# PS.net
KiCad netlist of a schematic drawn in Altium Designer
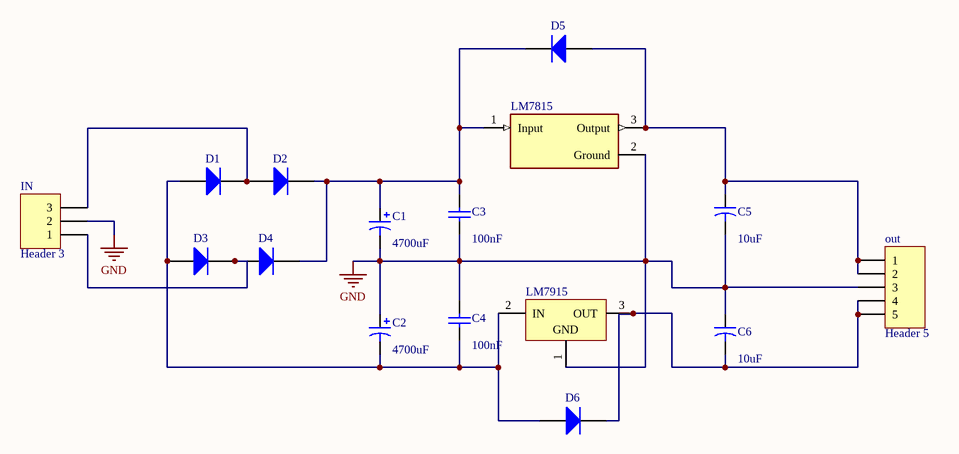
[diagram p0: PS.SchDoc]

(export (version "E")
  (design (tool "Eeschema 10.0.6"))
  (components
    (comp (ref "C1")
      (value "4700uF")
      (footprint "RB7.6-15")
      (description "Polarized Capacitor (Radial)")
      (fields (field (name "Comment") "Cap Pol1") (field (name "PUBLISHER") "Altium Limited"))
      (libsource (lib "Miscellaneous Devices") (part "Cap Pol1"))
    )
    (comp (ref "C2")
      (value "4700uF")
      (footprint "RB7.6-15")
      (description "Polarized Capacitor (Radial)")
      (fields (field (name "Comment") "Cap Pol1") (field (name "PUBLISHER") "Altium Limited"))
      (libsource (lib "Miscellaneous Devices") (part "Cap Pol1"))
    )
    (comp (ref "C3")
      (value "100nF")
      (footprint "RAD-0.3")
      (description "Capacitor")
      (fields (field (name "Comment") "Cap") (field (name "PUBLISHER") "Altium Limited"))
      (libsource (lib "Miscellaneous Devices") (part "Cap"))
    )
    (comp (ref "C4")
      (value "100nF")
      (footprint "RAD-0.3")
      (description "Capacitor")
      (fields (field (name "Comment") "Cap") (field (name "PUBLISHER") "Altium Limited"))
      (libsource (lib "Miscellaneous Devices") (part "Cap"))
    )
    (comp (ref "C5")
      (value "10uF")
      (footprint "CAPR5-4X5")
      (description "Capacitor")
      (fields (field (name "Comment") "Cap2") (field (name "PUBLISHER") "Altium Limited"))
      (libsource (lib "Miscellaneous Devices") (part "Cap2"))
    )
    (comp (ref "C6")
      (value "10uF")
      (footprint "CAPR5-4X5")
      (description "Capacitor")
      (fields (field (name "Comment") "Cap2") (field (name "PUBLISHER") "Altium Limited"))
      (libsource (lib "Miscellaneous Devices") (part "Cap2"))
    )
    (comp (ref "D1")
      (value "Diode 1N4004")
      (footprint "DO-41")
      (description "1 Amp General Purpose Rectifier")
      (fields (field (name "PUBLISHER") "Altium Limited"))
      (libsource (lib "Miscellaneous Devices") (part "Diode 1N4004"))
    )
    (comp (ref "D2")
      (value "Diode 1N4004")
      (footprint "DO-41")
      (description "1 Amp General Purpose Rectifier")
      (fields (field (name "PUBLISHER") "Altium Limited"))
      (libsource (lib "Miscellaneous Devices") (part "Diode 1N4004"))
    )
    (comp (ref "D3")
      (value "Diode 1N4004")
      (footprint "DO-41")
      (description "1 Amp General Purpose Rectifier")
      (fields (field (name "PUBLISHER") "Altium Limited"))
      (libsource (lib "Miscellaneous Devices") (part "Diode 1N4004"))
    )
    (comp (ref "D4")
      (value "Diode 1N4004")
      (footprint "DO-41")
      (description "1 Amp General Purpose Rectifier")
      (fields (field (name "PUBLISHER") "Altium Limited"))
      (libsource (lib "Miscellaneous Devices") (part "Diode 1N4004"))
    )
    (comp (ref "D5")
      (value "Diode 1N4004")
      (footprint "DO-41")
      (description "1 Amp General Purpose Rectifier")
      (fields (field (name "PUBLISHER") "Altium Limited"))
      (libsource (lib "Miscellaneous Devices") (part "Diode 1N4004"))
    )
    (comp (ref "D6")
      (value "Diode 1N4004")
      (footprint "DO-41")
      (description "1 Amp General Purpose Rectifier")
      (fields (field (name "PUBLISHER") "Altium Limited"))
      (libsource (lib "Miscellaneous Devices") (part "Diode 1N4004"))
    )
    (comp (ref "IN")
      (value "Header 3")
      (footprint "HDR1X3")
      (description "Header, 3-Pin")
      (fields (field (name "PUBLISHER") "Altium Limited"))
      (libsource (lib "Miscellaneous Connectors") (part "Header 3"))
    )
    (comp (ref "LM7815")
      (value "LM7815")
      (footprint "FP-NDE0003B-MFG")
      (description "pin 1 in\r\npin 2 GND\r\npin 3 out")
      (fields
        (field (name "MANUFACTURER PART NUMBER") "LM7815CT/NOPB")
        (field (name "MANUFACTURER") "Texas Instruments")
      )
      (libsource (lib "Altium Content Vault") (part "5999f7a707ee989105d025204f4d0ef"))
    )
    (comp (ref "LM7915")
      (value "LM7915")
      (footprint "NDE0003A")
      (description "pin 3 out\r\npin 2 in \r\npin 1 GND")
      (fields (field (name "MANUFACTURER") "Texas Instruments"))
      (libsource (lib "Altium Content Vault") (part "PM-REG-LM7905-SIL3"))
    )
    (comp (ref "out")
      (value "Header 5")
      (footprint "HDR1X5")
      (description "Header, 5-Pin")
      (fields (field (name "PUBLISHER") "Altium Limited"))
      (libsource (lib "Miscellaneous Connectors") (part "Header 5"))
    )
  )
  (nets
    (net (code "1") (name "GND") (class "Default")
      (node (ref "C1") (pin "2") (pinfunction "2_2") (pintype "passive"))
      (node (ref "C2") (pin "1") (pinfunction "1_1") (pintype "passive"))
      (node (ref "C3") (pin "1") (pinfunction "1_1") (pintype "passive"))
      (node (ref "C4") (pin "2") (pinfunction "2_2") (pintype "passive"))
      (node (ref "C5") (pin "2") (pinfunction "2_2") (pintype "passive"))
      (node (ref "C6") (pin "1") (pinfunction "1_1") (pintype "passive"))
      (node (ref "IN") (pin "2") (pinfunction "2_2") (pintype "passive"))
      (node (ref "LM7815") (pin "2") (pinfunction "Ground_2") (pintype "power_in"))
      (node (ref "LM7915") (pin "1") (pinfunction "GND_1") (pintype "power_in"))
      (node (ref "out") (pin "3") (pinfunction "3_3") (pintype "passive"))
    )
    (net (code "2") (name "Net-(D1-A)") (class "Default")
      (node (ref "C2") (pin "2") (pinfunction "2_2") (pintype "passive"))
      (node (ref "C4") (pin "1") (pinfunction "1_1") (pintype "passive"))
      (node (ref "D1") (pin "1") (pinfunction "A_1") (pintype "passive"))
      (node (ref "D3") (pin "1") (pinfunction "A_1") (pintype "passive"))
      (node (ref "D6") (pin "1") (pinfunction "A_1") (pintype "passive"))
      (node (ref "LM7915") (pin "2") (pinfunction "IN_2") (pintype "power_in"))
    )
    (net (code "3") (name "Net-(D1-K)") (class "Default")
      (node (ref "D1") (pin "2") (pinfunction "K_2") (pintype "passive"))
      (node (ref "D2") (pin "1") (pinfunction "A_1") (pintype "passive"))
      (node (ref "IN") (pin "3") (pinfunction "3_3") (pintype "passive"))
    )
    (net (code "4") (name "Net-(D2-K)") (class "Default")
      (node (ref "C1") (pin "1") (pinfunction "1_1") (pintype "passive"))
      (node (ref "C3") (pin "2") (pinfunction "2_2") (pintype "passive"))
      (node (ref "D2") (pin "2") (pinfunction "K_2") (pintype "passive"))
      (node (ref "D4") (pin "2") (pinfunction "K_2") (pintype "passive"))
      (node (ref "D5") (pin "2") (pinfunction "K_2") (pintype "passive"))
      (node (ref "LM7815") (pin "1") (pinfunction "Input_1") (pintype "input"))
    )
    (net (code "5") (name "Net-(D3-K)") (class "Default")
      (node (ref "D3") (pin "2") (pinfunction "K_2") (pintype "passive"))
      (node (ref "D4") (pin "1") (pinfunction "A_1") (pintype "passive"))
      (node (ref "IN") (pin "1") (pinfunction "1_1") (pintype "passive"))
    )
    (net (code "6") (name "Net-(D5-A)") (class "Default")
      (node (ref "C5") (pin "1") (pinfunction "1_1") (pintype "passive"))
      (node (ref "D5") (pin "1") (pinfunction "A_1") (pintype "passive"))
      (node (ref "LM7815") (pin "3") (pinfunction "Output_3") (pintype "output"))
      (node (ref "out") (pin "1") (pinfunction "1_1") (pintype "passive"))
      (node (ref "out") (pin "2") (pinfunction "2_2") (pintype "passive"))
    )
    (net (code "7") (name "Net-(D6-K)") (class "Default")
      (node (ref "C6") (pin "2") (pinfunction "2_2") (pintype "passive"))
      (node (ref "D6") (pin "2") (pinfunction "K_2") (pintype "passive"))
      (node (ref "LM7915") (pin "3") (pinfunction "OUT_3") (pintype "power_in"))
      (node (ref "out") (pin "4") (pinfunction "4_4") (pintype "passive"))
      (node (ref "out") (pin "5") (pinfunction "5_5") (pintype "passive"))
    )
  )
)
